# Voltage_DC.net
KiCad netlist of a schematic drawn in Altium Designer
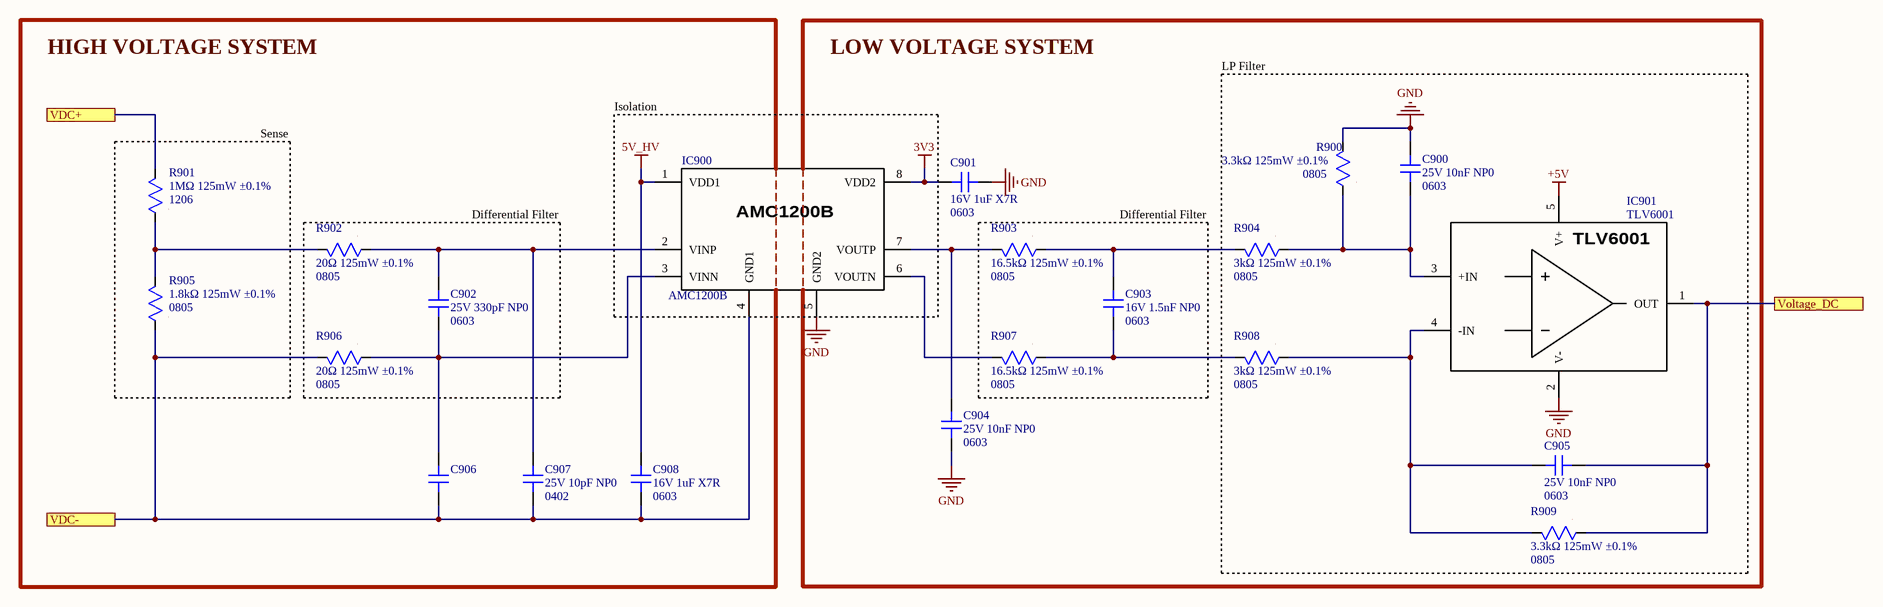
[diagram p0: Voltage_DC.SchDoc]

(export (version "E")
  (design (tool "Eeschema 10.0.6"))
  (components
    (comp (ref "C900")
      (value "25V 10nF NP0")
      (footprint "CAP SMD 0603")
      (description "Condensadores de cerámica multicapa (MLCC- SMD/SMT) 0.01 uF 25 VDC 1% 0603 C0G (NP0) AEC-Q200")
      (fields
        (field (name "PACKAGE") "0603")
        (field (name "MPN") "GRT1885C1E103FA02D")
        (field (name "MANUFACTURER") "muRata")
      )
      (libsource (lib "eUSR_Database") (part "CAP non polarized"))
    )
    (comp (ref "C901")
      (value "16V 1uF X7R")
      (footprint "CAP SMD 0603")
      (description "Condensadores de cerámica multicapa (MLCC- SMD/SMT) WCAP-CSGP 1uF 0603 10% 16V MLCC")
      (fields
        (field (name "PACKAGE") "0603")
        (field (name "MPN") "885012206052")
        (field (name "MANUFACTURER") "Wurth Elektronik")
      )
      (libsource (lib "eUSR_Database") (part "CAP non polarized"))
    )
    (comp (ref "C902")
      (value "25V 330pF NP0")
      (footprint "CAP SMD 0603")
      (description "Condensadores de cerámica multicapa (MLCC- SMD/SMT) 0603 330pF 25volts C0G 1%")
      (fields
        (field (name "PACKAGE") "0603")
        (field (name "MPN") "VJ0603A331FXXCW1BC")
        (field (name "MANUFACTURER") "Vishay")
      )
      (libsource (lib "eUSR_Database") (part "CAP non polarized"))
    )
    (comp (ref "C903")
      (value "16V 1.5nF NP0")
      (footprint "CAP SMD 0603")
      (description "Condensadores de cerámica multicapa (MLCC- SMD/SMT) 25V 1500pF C0G 0603 1%")
      (fields
        (field (name "PACKAGE") "0603")
        (field (name "MPN") "C0603C152F3GECTU")
        (field (name "MANUFACTURER") "KEMET")
      )
      (libsource (lib "eUSR_Database") (part "CAP non polarized"))
    )
    (comp (ref "C904")
      (value "25V 10nF NP0")
      (footprint "CAP SMD 0603")
      (description "Condensadores de cerámica multicapa (MLCC- SMD/SMT) 50V 5100pF 0603 C0G 1%")
      (fields
        (field (name "PACKAGE") "0603")
        (field (name "MPN") "C0603C512F5GACTU")
        (field (name "MANUFACTURER") "KEMET")
      )
      (libsource (lib "eUSR_Database") (part "CAP non polarized"))
    )
    (comp (ref "C905")
      (value "25V 10nF NP0")
      (footprint "CAP SMD 0603")
      (description "Condensadores de cerámica multicapa (MLCC- SMD/SMT) 0.01 uF 25 VDC 1% 0603 C0G (NP0) AEC-Q200")
      (fields
        (field (name "PACKAGE") "0603")
        (field (name "MPN") "GRT1885C1E103FA02D")
        (field (name "MANUFACTURER") "muRata")
      )
      (libsource (lib "eUSR_Database") (part "CAP non polarized"))
    )
    (comp (ref "C906")
      (value "CAP non polarized")
      (footprint "CAP SMD 0402")
      (description "Condensadores de cerámica multicapa (MLCC- SMD/SMT) 25V 10pF C0G 0402 0. 1pF")
      (fields (field (name "MPN") "04023A100BAT2A") (field (name "MANUFACTURER") "KYOCERA AVX"))
      (libsource (lib "eUSR_Database") (part "CAP non polarized"))
    )
    (comp (ref "C907")
      (value "25V 10pF NP0")
      (footprint "CAP SMD 0402")
      (description "Condensadores de cerámica multicapa (MLCC- SMD/SMT) 25V 10pF C0G 0402 0. 1pF")
      (fields
        (field (name "PACKAGE") "0402")
        (field (name "MPN") "04023A100BAT2A")
        (field (name "MANUFACTURER") "KYOCERA AVX")
      )
      (libsource (lib "eUSR_Database") (part "CAP non polarized"))
    )
    (comp (ref "C908")
      (value "16V 1uF X7R")
      (footprint "CAP SMD 0603")
      (description "Condensadores de cerámica multicapa (MLCC- SMD/SMT) WCAP-CSGP 1uF 0603 10% 16V MLCC")
      (fields
        (field (name "PACKAGE") "0603")
        (field (name "MPN") "885012206052")
        (field (name "MANUFACTURER") "Wurth Elektronik")
      )
      (libsource (lib "eUSR_Database") (part "CAP non polarized"))
    )
    (comp (ref "IC900")
      (value "AMC1200B")
      (footprint "AMC1200B")
      (description "Amplificadores de aislamiento 4kV peak Iso Amp A 5 95-AMC1200BDUB A 59 A 595-AMC1200BDUB")
      (fields (field (name "MPN") "AMC1200BDUBR") (field (name "MANUFACTURER") "Texas Instruments"))
      (libsource (lib "eUSR_Database") (part "AMC1200B"))
    )
    (comp (ref "IC901")
      (value "TLV6001")
      (footprint "SOT-23-5")
      (fields (field (name "MPN") "TLV6001UIDBVR") (field (name "MANUFACTURER") "Texas Instruments"))
      (libsource (lib "eUSR_Database") (part "TLV6001"))
    )
    (comp (ref "R900")
      (value "3.3kΩ 125mW ±0.1%")
      (footprint "RES SMD 0805")
      (description "Thin Film Resistors 0805 3.3Kohm 0.1% 15ppm AEC-Q200")
      (fields
        (field (name "PACKAGE") "0805")
        (field (name "MPN") "ERA-6APB332V")
        (field (name "MANUFACTURER") "Panasonic")
      )
      (libsource (lib "eUSR_Database") (part "RES"))
    )
    (comp (ref "R901")
      (value "1MΩ 125mW ±0.1%")
      (footprint "RES SMD 1206")
      (description "Thin Film Resistors CHIP RESISTOR Precision")
      (fields
        (field (name "PACKAGE") "1206")
        (field (name "MPN") "CRT1206-BW-1004ELF")
        (field (name "MANUFACTURER") "Bourns")
      )
      (libsource (lib "eUSR_Database") (part "RES"))
    )
    (comp (ref "R902")
      (value "20Ω 125mW ±0.1%")
      (footprint "RES SMD 0805")
      (description "Thin Film Resistors RP 2A 20R 0.1% 15PPM CUT LENGTH")
      (fields
        (field (name "PACKAGE") "0805")
        (field (name "MPN") "RP73D2A20RBTG")
        (field (name "MANUFACTURER") "TE")
      )
      (libsource (lib "eUSR_Database") (part "RES"))
    )
    (comp (ref "R903")
      (value "16.5kΩ 125mW ±0.1%")
      (footprint "RES SMD 0805")
      (description "Thin Film Resistors 0805 Thin film chip resistor")
      (fields
        (field (name "PACKAGE") "0805")
        (field (name "MPN") "ERA-6ARB1652V")
        (field (name "MANUFACTURER") "Panasonic")
      )
      (libsource (lib "eUSR_Database") (part "RES"))
    )
    (comp (ref "R904")
      (value "3kΩ 125mW ±0.1%")
      (footprint "RES SMD 0805")
      (description "Thin Film Resistors 0805 3Kohm 0.1% 15ppm AEC-Q200")
      (fields
        (field (name "PACKAGE") "0805")
        (field (name "MPN") "ERA-6APB302V")
        (field (name "MANUFACTURER") "Panasonic")
      )
      (libsource (lib "eUSR_Database") (part "RES"))
    )
    (comp (ref "R905")
      (value "1.8kΩ 125mW ±0.1%")
      (footprint "RES SMD 0805")
      (description "Thin Film Resistors 0805 1.8Kohm 0.1% 10ppm AEC-Q200")
      (fields
        (field (name "PACKAGE") "0805")
        (field (name "MPN") "ERA-6ARB182V")
        (field (name "MANUFACTURER") "Panasonic")
      )
      (libsource (lib "eUSR_Database") (part "RES"))
    )
    (comp (ref "R906")
      (value "20Ω 125mW ±0.1%")
      (footprint "RES SMD 0805")
      (description "Thin Film Resistors RP 2A 20R 0.1% 15PPM CUT LENGTH")
      (fields
        (field (name "PACKAGE") "0805")
        (field (name "MPN") "RP73D2A20RBTG")
        (field (name "MANUFACTURER") "TE")
      )
      (libsource (lib "eUSR_Database") (part "RES"))
    )
    (comp (ref "R907")
      (value "16.5kΩ 125mW ±0.1%")
      (footprint "RES SMD 0805")
      (description "Thin Film Resistors 0805 Thin film chip resistor")
      (fields
        (field (name "PACKAGE") "0805")
        (field (name "MPN") "ERA-6ARB1652V")
        (field (name "MANUFACTURER") "Panasonic")
      )
      (libsource (lib "eUSR_Database") (part "RES"))
    )
    (comp (ref "R908")
      (value "3kΩ 125mW ±0.1%")
      (footprint "RES SMD 0805")
      (description "Thin Film Resistors 0805 3Kohm 0.1% 15ppm AEC-Q200")
      (fields
        (field (name "PACKAGE") "0805")
        (field (name "MPN") "ERA-6APB302V")
        (field (name "MANUFACTURER") "Panasonic")
      )
      (libsource (lib "eUSR_Database") (part "RES"))
    )
    (comp (ref "R909")
      (value "3.3kΩ 125mW ±0.1%")
      (footprint "RES SMD 0805")
      (description "Thin Film Resistors 0805 3.3Kohm 0.1% 15ppm AEC-Q200")
      (fields
        (field (name "PACKAGE") "0805")
        (field (name "MPN") "ERA-6APB332V")
        (field (name "MANUFACTURER") "Panasonic")
      )
      (libsource (lib "eUSR_Database") (part "RES"))
    )
  )
  (nets
    (net (code "1") (name "+5V") (class "Default")
      (node (ref "IC901") (pin "5") (pinfunction "V+_5") (pintype "passive"))
    )
    (net (code "2") (name "/VDC+") (class "Default")
      (node (ref "R901") (pin "2") (pinfunction "2_2") (pintype "passive"))
    )
    (net (code "3") (name "/VDC-") (class "Default")
      (node (ref "C906") (pin "2") (pinfunction "2_2") (pintype "passive"))
      (node (ref "C907") (pin "2") (pinfunction "2_2") (pintype "passive"))
      (node (ref "C908") (pin "2") (pinfunction "2_2") (pintype "passive"))
      (node (ref "IC900") (pin "4") (pinfunction "GND1_4") (pintype "passive"))
      (node (ref "R905") (pin "1") (pinfunction "1_1") (pintype "passive"))
      (node (ref "R906") (pin "2") (pinfunction "2_2") (pintype "passive"))
    )
    (net (code "4") (name "/Voltage_DC") (class "Default")
      (node (ref "C905") (pin "2") (pinfunction "2_2") (pintype "passive"))
      (node (ref "IC901") (pin "1") (pinfunction "OUT_1") (pintype "passive"))
      (node (ref "R909") (pin "1") (pinfunction "1_1") (pintype "passive"))
    )
    (net (code "5") (name "3V3") (class "Default")
      (node (ref "C901") (pin "1") (pinfunction "1_1") (pintype "passive"))
      (node (ref "IC900") (pin "8") (pinfunction "VDD2_8") (pintype "passive"))
    )
    (net (code "6") (name "5V_HV") (class "Default")
      (node (ref "C908") (pin "1") (pinfunction "1_1") (pintype "passive"))
      (node (ref "IC900") (pin "1") (pinfunction "VDD1_1") (pintype "passive"))
    )
    (net (code "7") (name "GND") (class "Default")
      (node (ref "C900") (pin "2") (pinfunction "2_2") (pintype "passive"))
      (node (ref "C901") (pin "2") (pinfunction "2_2") (pintype "passive"))
      (node (ref "C904") (pin "2") (pinfunction "2_2") (pintype "passive"))
      (node (ref "IC900") (pin "5") (pinfunction "GND2_5") (pintype "passive"))
      (node (ref "IC901") (pin "2") (pinfunction "V-_2") (pintype "passive"))
      (node (ref "R900") (pin "2") (pinfunction "2_2") (pintype "passive"))
    )
    (net (code "8") (name "Net-(C903-Pad1)") (class "Default")
      (node (ref "C903") (pin "1") (pinfunction "1_1") (pintype "passive"))
      (node (ref "R903") (pin "1") (pinfunction "1_1") (pintype "passive"))
      (node (ref "R904") (pin "2") (pinfunction "2_2") (pintype "passive"))
    )
    (net (code "9") (name "Net-(C903-Pad2)") (class "Default")
      (node (ref "C903") (pin "2") (pinfunction "2_2") (pintype "passive"))
      (node (ref "R907") (pin "1") (pinfunction "1_1") (pintype "passive"))
      (node (ref "R908") (pin "2") (pinfunction "2_2") (pintype "passive"))
    )
    (net (code "10") (name "Net-(IC900-VINN)") (class "Default")
      (node (ref "C902") (pin "2") (pinfunction "2_2") (pintype "passive"))
      (node (ref "C906") (pin "1") (pinfunction "1_1") (pintype "passive"))
      (node (ref "IC900") (pin "3") (pinfunction "VINN_3") (pintype "passive"))
      (node (ref "R906") (pin "1") (pinfunction "1_1") (pintype "passive"))
    )
    (net (code "11") (name "Net-(IC900-VINP)") (class "Default")
      (node (ref "C902") (pin "1") (pinfunction "1_1") (pintype "passive"))
      (node (ref "C907") (pin "1") (pinfunction "1_1") (pintype "passive"))
      (node (ref "IC900") (pin "2") (pinfunction "VINP_2") (pintype "passive"))
      (node (ref "R902") (pin "1") (pinfunction "1_1") (pintype "passive"))
    )
    (net (code "12") (name "Net-(IC900-VOUTN)") (class "Default")
      (node (ref "IC900") (pin "6") (pinfunction "VOUTN_6") (pintype "passive"))
      (node (ref "R907") (pin "2") (pinfunction "2_2") (pintype "passive"))
    )
    (net (code "13") (name "Net-(IC900-VOUTP)") (class "Default")
      (node (ref "C904") (pin "1") (pinfunction "1_1") (pintype "passive"))
      (node (ref "IC900") (pin "7") (pinfunction "VOUTP_7") (pintype "passive"))
      (node (ref "R903") (pin "2") (pinfunction "2_2") (pintype "passive"))
    )
    (net (code "14") (name "Net-(IC901-+IN)") (class "Default")
      (node (ref "C900") (pin "1") (pinfunction "1_1") (pintype "passive"))
      (node (ref "IC901") (pin "3") (pinfunction "+IN_3") (pintype "passive"))
      (node (ref "R900") (pin "1") (pinfunction "1_1") (pintype "passive"))
      (node (ref "R904") (pin "1") (pinfunction "1_1") (pintype "passive"))
    )
    (net (code "15") (name "Net-(IC901--IN)") (class "Default")
      (node (ref "C905") (pin "1") (pinfunction "1_1") (pintype "passive"))
      (node (ref "IC901") (pin "4") (pinfunction "-IN_4") (pintype "passive"))
      (node (ref "R908") (pin "1") (pinfunction "1_1") (pintype "passive"))
      (node (ref "R909") (pin "2") (pinfunction "2_2") (pintype "passive"))
    )
    (net (code "16") (name "Net-(R901-Pad1)") (class "Default")
      (node (ref "R901") (pin "1") (pinfunction "1_1") (pintype "passive"))
      (node (ref "R902") (pin "2") (pinfunction "2_2") (pintype "passive"))
      (node (ref "R905") (pin "2") (pinfunction "2_2") (pintype "passive"))
    )
  )
)
